# gtfo_shoo.net
KiCad netlist of a schematic drawn in EAGLE
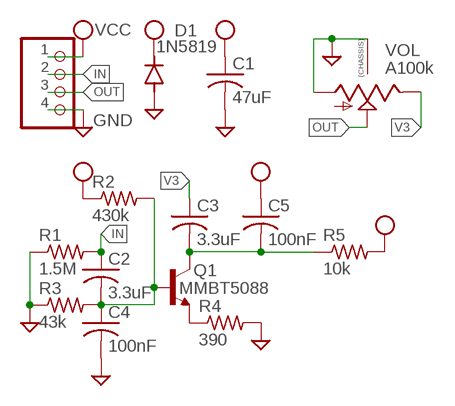
[diagram p0: schematic, sheet 1]

(export (version "E")
  (design (tool "Eeschema 10.0.6"))
  (components
    (comp (ref "C1")
      (value "47uF")
      (footprint "eagle-import:C1210")
      (libsource (lib "eagle-import") (part "adafruit_420_C-USC1210"))
    )
    (comp (ref "C2")
      (value "3.3uF")
      (footprint "eagle-import:C0805")
      (libsource (lib "eagle-import") (part "C-USC0805"))
    )
    (comp (ref "C3")
      (value "3.3uF")
      (footprint "eagle-import:C0805")
      (libsource (lib "eagle-import") (part "C-USC0805"))
    )
    (comp (ref "C4")
      (value "100nF")
      (footprint "eagle-import:C0603")
      (libsource (lib "eagle-import") (part "adafruit_420_C-USC0603"))
    )
    (comp (ref "C5")
      (value "100nF")
      (footprint "eagle-import:C0603")
      (libsource (lib "eagle-import") (part "adafruit_420_C-USC0603"))
    )
    (comp (ref "D1")
      (value "1N5819")
      (footprint "eagle-import:SOD123")
      (libsource (lib "eagle-import") (part "DIODE-SOD123"))
    )
    (comp (ref "JP1")
      (value "PINHD-1X4")
      (footprint "eagle-import:1X04")
      (libsource (lib "eagle-import") (part "PINHD-1X4"))
    )
    (comp (ref "Q1")
      (value "MMBT5088")
      (footprint "eagle-import:SOT23-BEC")
      (fields (field (name "MF") "ON Semiconductor"))
      (libsource (lib "eagle-import") (part "MMBT5088"))
    )
    (comp (ref "R1")
      (value "1.5M")
      (footprint "eagle-import:R0603")
      (libsource (lib "eagle-import") (part "R-US_R0603"))
    )
    (comp (ref "R2")
      (value "430k")
      (footprint "eagle-import:R0603")
      (libsource (lib "eagle-import") (part "R-US_R0603"))
    )
    (comp (ref "R3")
      (value "43k")
      (footprint "eagle-import:R0603")
      (libsource (lib "eagle-import") (part "R-US_R0603"))
    )
    (comp (ref "R4")
      (value "390")
      (footprint "eagle-import:R0603")
      (libsource (lib "eagle-import") (part "R-US_R0603"))
    )
    (comp (ref "R5")
      (value "10k")
      (footprint "eagle-import:R0603")
      (libsource (lib "eagle-import") (part "R-US_R0603"))
    )
    (comp (ref "VOL")
      (value "A100k")
      (footprint "eagle-import:9MM_SNAP-IN_POT")
      (libsource (lib "eagle-import") (part "9MM_SNAP-IN_POT_CHASSIS"))
    )
  )
  (nets
    (net (code "1") (name "GND") (class "Default")
      (node (ref "C1") (pin "2") (pinfunction "2_2") (pintype "passive"))
      (node (ref "C4") (pin "2") (pinfunction "2_2") (pintype "passive"))
      (node (ref "D1") (pin "A") (pinfunction "A_A") (pintype "passive"))
      (node (ref "JP1") (pin "4") (pinfunction "4_4") (pintype "passive"))
      (node (ref "R1") (pin "1") (pinfunction "1_1") (pintype "passive"))
      (node (ref "R3") (pin "1") (pinfunction "1_1") (pintype "passive"))
      (node (ref "R4") (pin "2") (pinfunction "2_2") (pintype "passive"))
      (node (ref "VOL") (pin "1") (pinfunction "A_1") (pintype "passive"))
      (node (ref "VOL") (pin "CHASSIS1") (pinfunction "P$1_CHASSIS1") (pintype "passive"))
      (node (ref "VOL") (pin "CHASSIS2") (pinfunction "P$1_CHASSIS2") (pintype "passive"))
    )
    (net (code "2") (name "IN") (class "Default")
      (node (ref "C2") (pin "1") (pinfunction "1_1") (pintype "passive"))
      (node (ref "JP1") (pin "2") (pinfunction "2_2") (pintype "passive"))
      (node (ref "R1") (pin "2") (pinfunction "2_2") (pintype "passive"))
    )
    (net (code "3") (name "Net-(C2-Pad2)") (class "Default")
      (node (ref "C2") (pin "2") (pinfunction "2_2") (pintype "passive"))
      (node (ref "C4") (pin "1") (pinfunction "1_1") (pintype "passive"))
      (node (ref "Q1") (pin "B") (pinfunction "B_B") (pintype "passive"))
      (node (ref "R2") (pin "2") (pinfunction "2_2") (pintype "passive"))
      (node (ref "R3") (pin "2") (pinfunction "2_2") (pintype "passive"))
    )
    (net (code "4") (name "Net-(C3-Pad2)") (class "Default")
      (node (ref "C3") (pin "2") (pinfunction "2_2") (pintype "passive"))
      (node (ref "C5") (pin "2") (pinfunction "2_2") (pintype "passive"))
      (node (ref "Q1") (pin "C") (pinfunction "C_C") (pintype "passive"))
      (node (ref "R5") (pin "1") (pinfunction "1_1") (pintype "passive"))
    )
    (net (code "5") (name "Net-(Q1-PadE)") (class "Default")
      (node (ref "Q1") (pin "E") (pinfunction "E_E") (pintype "passive"))
      (node (ref "R4") (pin "1") (pinfunction "1_1") (pintype "passive"))
    )
    (net (code "6") (name "OUT") (class "Default")
      (node (ref "JP1") (pin "3") (pinfunction "3_3") (pintype "passive"))
      (node (ref "VOL") (pin "2") (pinfunction "S_2") (pintype "passive"))
    )
    (net (code "7") (name "V3") (class "Default")
      (node (ref "C3") (pin "1") (pinfunction "1_1") (pintype "passive"))
      (node (ref "VOL") (pin "3") (pinfunction "E_3") (pintype "passive"))
    )
    (net (code "8") (name "VCC") (class "Default")
      (node (ref "C1") (pin "1") (pinfunction "1_1") (pintype "passive"))
      (node (ref "C5") (pin "1") (pinfunction "1_1") (pintype "passive"))
      (node (ref "D1") (pin "C") (pinfunction "C_C") (pintype "passive"))
      (node (ref "JP1") (pin "1") (pinfunction "1_1") (pintype "passive"))
      (node (ref "R2") (pin "1") (pinfunction "1_1") (pintype "passive"))
      (node (ref "R5") (pin "2") (pinfunction "2_2") (pintype "passive"))
    )
  )
)
